# 5vBoost.net
KiCad netlist of a schematic drawn in Altium Designer
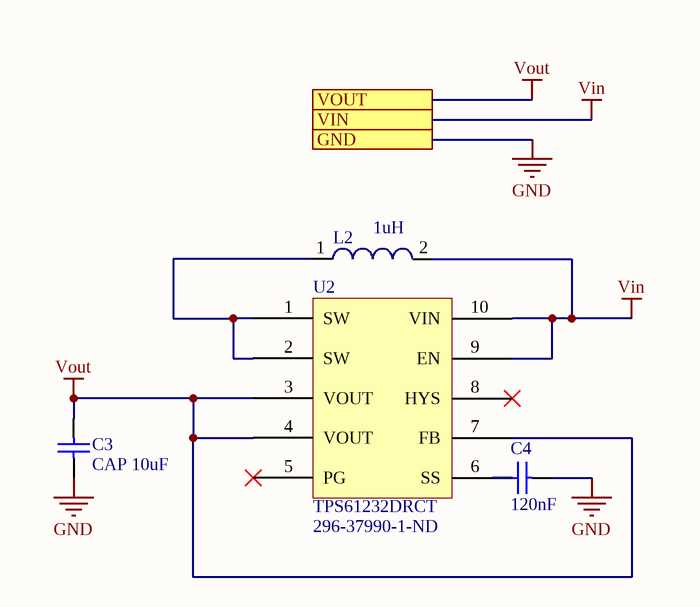
[diagram p0: 5vBoost.SchDoc]

(export (version "E")
  (design (tool "Eeschema 10.0.6"))
  (components
    (comp (ref "C3")
      (value "CAP 10uF")
      (footprint "CAPC0805(2012)145_L")
      (description "CAP 10uF 16V ±10% 0805 (2012 Metric) Thickness 1.45mm SMD")
      (fields (field (name "TOLERANCE") "Â±10%"))
      (libsource (lib "Altium Content Vault") (part "CAP"))
    )
    (comp (ref "C4")
      (value "120nF")
      (footprint "CAPC2013X140X50ML20T25")
      (fields
        (field (name "MANUFACTURER") "AVX Interconnect / Elco")
        (field (name "PART NUMBER") "08055C124KAT2A")
      )
      (libsource (lib "Altium Content Vault") (part "CAP"))
    )
    (comp (ref "L2")
      (value "1uH")
      (footprint "SMD 2510")
      (description "Power Multilayer Inductor WE-MAPI, L=1.0µH")
      (fields (field (name "MANUFACTURER") "Wuerth Elektronik") (field (name "PARTNUMBER") "74438323010"))
      (libsource (lib "Altium Content Vault") (part "WE-IND-INDUCTOR-2"))
    )
    (comp (ref "U2")
      (value "TPS61232DRCT")
      (footprint "*SON50P300X300X100-10N")
      (fields
        (field (name "MANUFACTURER") "Texas Instruments")
        (field (name "SUPPLIER PART NUMBER 1") "296-37990-1-ND")
      )
      (libsource (lib "5V_boost") (part "TPS61232DRCT"))
    )
  )
  (nets
    (net (code "1") (name "GND") (class "Default")
      (node (ref "C3") (pin "1") (pinfunction "1_1") (pintype "passive"))
      (node (ref "C4") (pin "2") (pinfunction "2_2") (pintype "passive"))
    )
    (net (code "2") (name "Net-(L2-Pad1)") (class "Default")
      (node (ref "L2") (pin "1") (pinfunction "1_1") (pintype "passive"))
      (node (ref "U2") (pin "1") (pinfunction "SW_1") (pintype "passive"))
      (node (ref "U2") (pin "2") (pinfunction "SW_2") (pintype "passive"))
    )
    (net (code "3") (name "Net-(U2-SS)") (class "Default")
      (node (ref "C4") (pin "1") (pinfunction "1_1") (pintype "passive"))
      (node (ref "U2") (pin "6") (pinfunction "SS_6") (pintype "passive"))
    )
    (net (code "4") (name "Vin") (class "Default")
      (node (ref "L2") (pin "2") (pinfunction "2_2") (pintype "passive"))
      (node (ref "U2") (pin "10") (pinfunction "VIN_10") (pintype "passive"))
      (node (ref "U2") (pin "9") (pinfunction "EN_9") (pintype "passive"))
    )
    (net (code "5") (name "Vout") (class "Default")
      (node (ref "C3") (pin "2") (pinfunction "2_2") (pintype "passive"))
      (node (ref "U2") (pin "3") (pinfunction "VOUT_3") (pintype "passive"))
      (node (ref "U2") (pin "4") (pinfunction "VOUT_4") (pintype "passive"))
      (node (ref "U2") (pin "7") (pinfunction "FB_7") (pintype "passive"))
    )
    (net (code "6") (name "unconnected-(U2-HYS-Pad8)") (class "Default")
      (node (ref "U2") (pin "8") (pinfunction "HYS_8") (pintype "passive+no_connect"))
    )
    (net (code "7") (name "unconnected-(U2-PG-Pad5)") (class "Default")
      (node (ref "U2") (pin "5") (pinfunction "PG_5") (pintype "passive+no_connect"))
    )
  )
)
